# solar.net
KiCad netlist of a schematic drawn in EAGLE
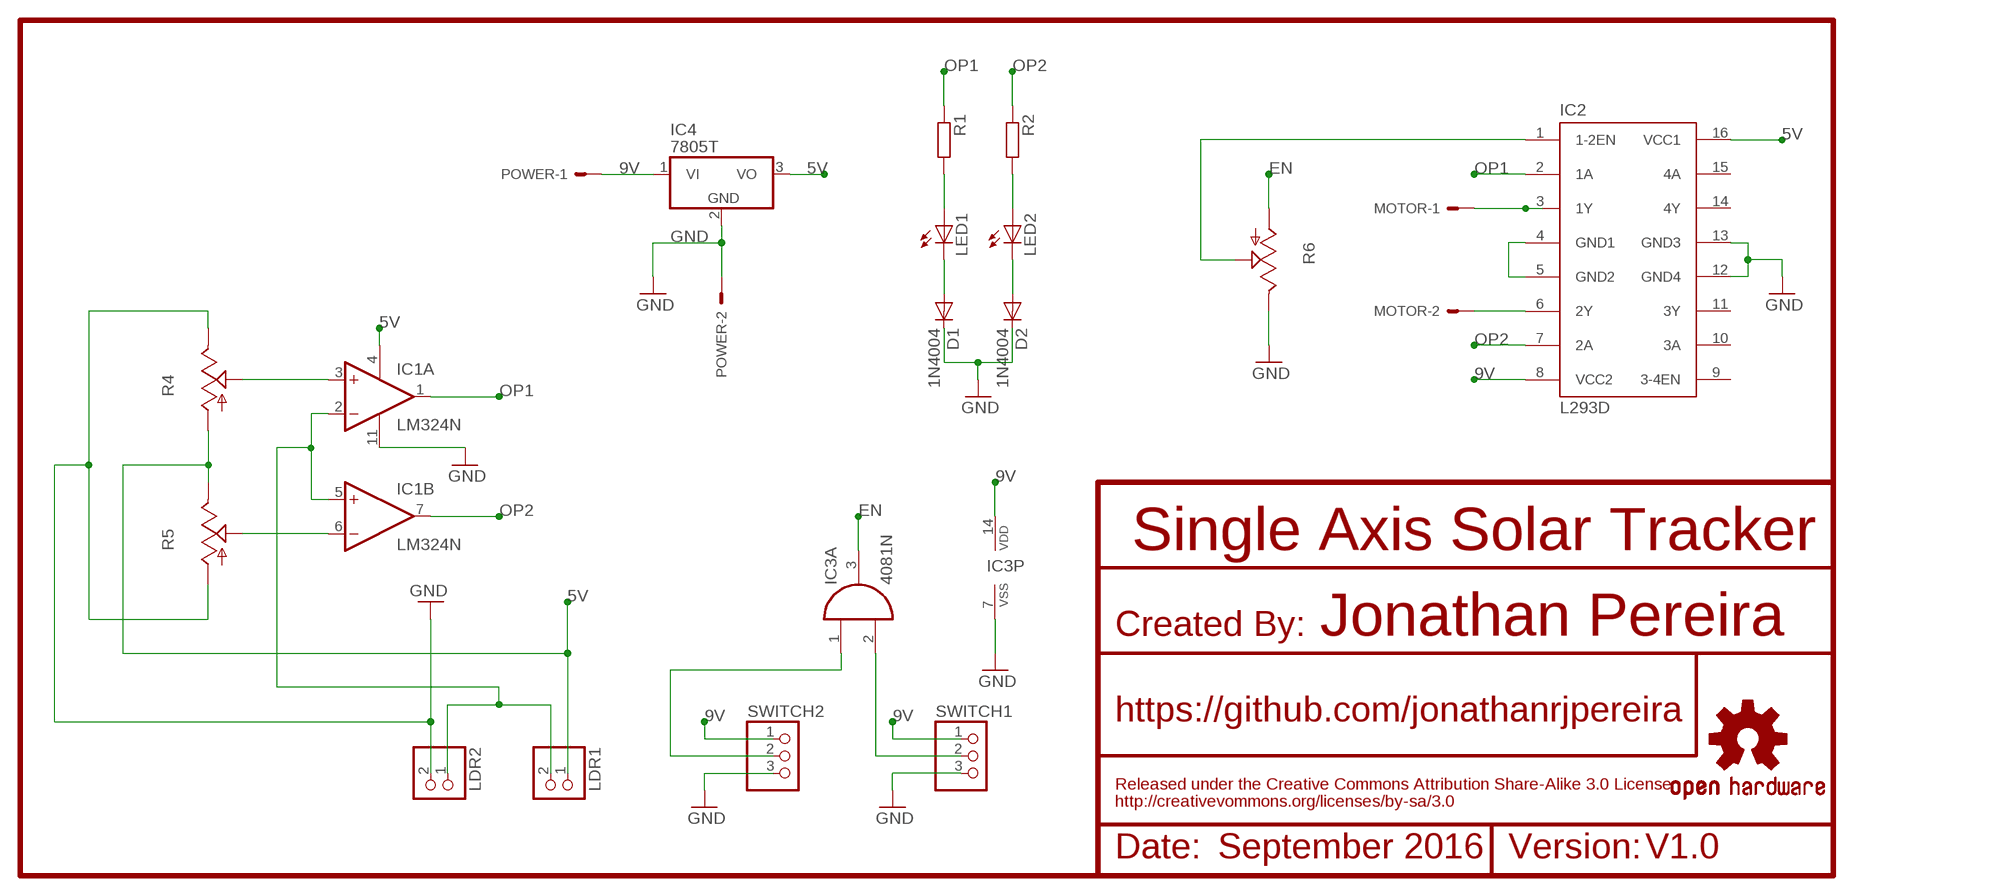
[diagram p0: schematic, sheet 1]

(export (version "E")
  (design (tool "Eeschema 10.0.6"))
  (components
    (comp (ref "D1")
      (value "1N4004")
      (footprint "eagle-import:DO41-10")
      (libsource (lib "eagle-import") (part "1N4004"))
    )
    (comp (ref "D2")
      (value "1N4004")
      (footprint "eagle-import:DO41-10")
      (libsource (lib "eagle-import") (part "1N4004"))
    )
    (comp (ref "IC1")
      (value "LM324N")
      (footprint "eagle-import:DIL14")
      (libsource (lib "eagle-import") (part "LM324N"))
    )
    (comp (ref "IC2")
      (value "L293D")
      (footprint "eagle-import:DIL16")
      (libsource (lib "eagle-import") (part "L293D"))
    )
    (comp (ref "IC3")
      (value "4081N")
      (footprint "eagle-import:DIL14")
      (libsource (lib "eagle-import") (part "4081N"))
    )
    (comp (ref "IC4")
      (value "7805T")
      (footprint "eagle-import:TO220H")
      (libsource (lib "eagle-import") (part "78T05"))
    )
    (comp (ref "LDR1")
      (value "PINHD-1X2")
      (footprint "eagle-import:1X02")
      (libsource (lib "eagle-import") (part "PINHD-1X2"))
    )
    (comp (ref "LDR2")
      (value "PINHD-1X2")
      (footprint "eagle-import:1X02")
      (libsource (lib "eagle-import") (part "PINHD-1X2"))
    )
    (comp (ref "LED1")
      (value "LED5MM")
      (footprint "eagle-import:LED5MM")
      (libsource (lib "eagle-import") (part "LED5MM"))
    )
    (comp (ref "LED2")
      (value "LED5MM")
      (footprint "eagle-import:LED5MM")
      (libsource (lib "eagle-import") (part "LED5MM"))
    )
    (comp (ref "LOGO1")
      (value "OSHW-LOGOL-COPPER")
      (footprint "eagle-import:OSHW-LOGO-L_COPPER")
      (libsource (lib "eagle-import") (part "OSHW-LOGOL-COPPER"))
    )
    (comp (ref "MOTOR")
      (value "KK-156-2")
      (footprint "eagle-import:KK-156-2")
      (libsource (lib "eagle-import") (part "KK-156-2"))
    )
    (comp (ref "POWER")
      (value "KK-156-2")
      (footprint "eagle-import:KK-156-2")
      (libsource (lib "eagle-import") (part "KK-156-2"))
    )
    (comp (ref "R1")
      (value "R-EU_0204/7")
      (footprint "eagle-import:0204_7")
      (libsource (lib "eagle-import") (part "R-EU_0204/7"))
    )
    (comp (ref "R2")
      (value "R-EU_0204/7")
      (footprint "eagle-import:0204_7")
      (libsource (lib "eagle-import") (part "R-EU_0204/7"))
    )
    (comp (ref "R4")
      (value "TRIM_US-CA6V")
      (footprint "eagle-import:CA6V")
      (libsource (lib "eagle-import") (part "TRIM_US-CA6V"))
    )
    (comp (ref "R5")
      (value "TRIM_US-CA6V")
      (footprint "eagle-import:CA6V")
      (libsource (lib "eagle-import") (part "TRIM_US-CA6V"))
    )
    (comp (ref "R6")
      (value "TRIM_US-CA6V")
      (footprint "eagle-import:CA6V")
      (libsource (lib "eagle-import") (part "TRIM_US-CA6V"))
    )
    (comp (ref "SWITCH1")
      (value "PINHD-1X3")
      (footprint "eagle-import:1X03")
      (libsource (lib "eagle-import") (part "PINHD-1X3"))
    )
    (comp (ref "SWITCH2")
      (value "PINHD-1X3")
      (footprint "eagle-import:1X03")
      (libsource (lib "eagle-import") (part "PINHD-1X3"))
    )
  )
  (nets
    (net (code "1") (name "/5V") (class "Default")
      (node (ref "IC1") (pin "4") (pinfunction "V+_4") (pintype "power_in"))
      (node (ref "IC2") (pin "16") (pinfunction "VCC1_16") (pintype "power_in"))
      (node (ref "IC4") (pin "3") (pinfunction "VO_3") (pintype "passive"))
      (node (ref "LDR1") (pin "1") (pinfunction "1_1") (pintype "passive"))
      (node (ref "R4") (pin "A") (pinfunction "A_A") (pintype "passive"))
      (node (ref "R5") (pin "E") (pinfunction "E_E") (pintype "passive"))
    )
    (net (code "2") (name "/9V") (class "Default")
      (node (ref "IC2") (pin "8") (pinfunction "VCC2_8") (pintype "power_in"))
      (node (ref "IC3") (pin "14") (pinfunction "VDD_14") (pintype "power_in"))
      (node (ref "IC4") (pin "1") (pinfunction "VI_1") (pintype "input"))
      (node (ref "POWER") (pin "1") (pinfunction "S_1") (pintype "passive"))
      (node (ref "SWITCH1") (pin "1") (pinfunction "1_1") (pintype "passive"))
      (node (ref "SWITCH2") (pin "1") (pinfunction "1_1") (pintype "passive"))
    )
    (net (code "3") (name "/EN") (class "Default")
      (node (ref "IC3") (pin "3") (pinfunction "O_3") (pintype "output"))
      (node (ref "R6") (pin "A") (pinfunction "A_A") (pintype "passive"))
    )
    (net (code "4") (name "/OP1") (class "Default")
      (node (ref "IC1") (pin "1") (pinfunction "OUT_1") (pintype "output"))
      (node (ref "IC2") (pin "2") (pinfunction "1A_2") (pintype "input"))
      (node (ref "R1") (pin "1") (pinfunction "1_1") (pintype "passive"))
    )
    (net (code "5") (name "/OP2") (class "Default")
      (node (ref "IC1") (pin "7") (pinfunction "OUT_7") (pintype "output"))
      (node (ref "IC2") (pin "7") (pinfunction "2A_7") (pintype "input"))
      (node (ref "R2") (pin "1") (pinfunction "1_1") (pintype "passive"))
    )
    (net (code "6") (name "GND") (class "Default")
      (node (ref "D1") (pin "C") (pinfunction "C_C") (pintype "passive"))
      (node (ref "D2") (pin "C") (pinfunction "C_C") (pintype "passive"))
      (node (ref "IC1") (pin "11") (pinfunction "V-_11") (pintype "power_in"))
      (node (ref "IC2") (pin "12") (pinfunction "GND4_12") (pintype "power_in"))
      (node (ref "IC2") (pin "13") (pinfunction "GND3_13") (pintype "power_in"))
      (node (ref "IC3") (pin "7") (pinfunction "VSS_7") (pintype "power_in"))
      (node (ref "IC4") (pin "2") (pinfunction "GND_2") (pintype "passive"))
      (node (ref "LDR2") (pin "2") (pinfunction "2_2") (pintype "passive"))
      (node (ref "POWER") (pin "2") (pinfunction "S_2") (pintype "passive"))
      (node (ref "R4") (pin "E") (pinfunction "E_E") (pintype "passive"))
      (node (ref "R5") (pin "A") (pinfunction "A_A") (pintype "passive"))
      (node (ref "R6") (pin "E") (pinfunction "E_E") (pintype "passive"))
      (node (ref "SWITCH1") (pin "3") (pinfunction "3_3") (pintype "passive"))
      (node (ref "SWITCH2") (pin "3") (pinfunction "3_3") (pintype "passive"))
    )
    (net (code "7") (name "Net-(IC1A-+IN)") (class "Default")
      (node (ref "IC1") (pin "3") (pinfunction "+IN_3") (pintype "input"))
      (node (ref "R4") (pin "S") (pinfunction "S_S") (pintype "passive"))
    )
    (net (code "8") (name "Net-(IC1A--IN)") (class "Default")
      (node (ref "IC1") (pin "2") (pinfunction "-IN_2") (pintype "input"))
      (node (ref "IC1") (pin "5") (pinfunction "+IN_5") (pintype "input"))
      (node (ref "LDR1") (pin "2") (pinfunction "2_2") (pintype "passive"))
      (node (ref "LDR2") (pin "1") (pinfunction "1_1") (pintype "passive"))
    )
    (net (code "9") (name "Net-(IC1B--IN)") (class "Default")
      (node (ref "IC1") (pin "6") (pinfunction "-IN_6") (pintype "input"))
      (node (ref "R5") (pin "S") (pinfunction "S_S") (pintype "passive"))
    )
    (net (code "10") (name "Net-(IC2-1-2EN)") (class "Default")
      (node (ref "IC2") (pin "1") (pinfunction "1-2EN_1") (pintype "input"))
      (node (ref "R6") (pin "S") (pinfunction "S_S") (pintype "passive"))
    )
    (net (code "11") (name "Net-(IC2-1Y)") (class "Default")
      (node (ref "IC2") (pin "3") (pinfunction "1Y_3") (pintype "output"))
      (node (ref "MOTOR") (pin "1") (pinfunction "S_1") (pintype "passive"))
    )
    (net (code "12") (name "Net-(IC2-2Y)") (class "Default")
      (node (ref "IC2") (pin "6") (pinfunction "2Y_6") (pintype "output"))
      (node (ref "MOTOR") (pin "2") (pinfunction "S_2") (pintype "passive"))
    )
    (net (code "13") (name "Net-(IC2-GND1)") (class "Default")
      (node (ref "IC2") (pin "4") (pinfunction "GND1_4") (pintype "power_in"))
      (node (ref "IC2") (pin "5") (pinfunction "GND2_5") (pintype "power_in"))
    )
    (net (code "14") (name "Net-(IC3A-I0)") (class "Default")
      (node (ref "IC3") (pin "1") (pinfunction "I0_1") (pintype "input"))
      (node (ref "SWITCH2") (pin "2") (pinfunction "2_2") (pintype "passive"))
    )
    (net (code "15") (name "Net-(IC3A-I1)") (class "Default")
      (node (ref "IC3") (pin "2") (pinfunction "I1_2") (pintype "input"))
      (node (ref "SWITCH1") (pin "2") (pinfunction "2_2") (pintype "passive"))
    )
    (net (code "16") (name "Net-(LED1-C)") (class "Default")
      (node (ref "D1") (pin "A") (pinfunction "A_A") (pintype "passive"))
      (node (ref "LED1") (pin "K") (pinfunction "C_K") (pintype "passive"))
    )
    (net (code "17") (name "Net-(LED1-PadA)") (class "Default")
      (node (ref "LED1") (pin "A") (pinfunction "A_A") (pintype "passive"))
      (node (ref "R1") (pin "2") (pinfunction "2_2") (pintype "passive"))
    )
    (net (code "18") (name "Net-(LED2-C)") (class "Default")
      (node (ref "D2") (pin "A") (pinfunction "A_A") (pintype "passive"))
      (node (ref "LED2") (pin "K") (pinfunction "C_K") (pintype "passive"))
    )
    (net (code "19") (name "Net-(LED2-PadA)") (class "Default")
      (node (ref "LED2") (pin "A") (pinfunction "A_A") (pintype "passive"))
      (node (ref "R2") (pin "2") (pinfunction "2_2") (pintype "passive"))
    )
    (net (code "20") (name "unconnected-(IC2-3-4EN-Pad9)") (class "Default")
      (node (ref "IC2") (pin "9") (pinfunction "3-4EN_9") (pintype "input"))
    )
    (net (code "21") (name "unconnected-(IC2-3A-Pad10)") (class "Default")
      (node (ref "IC2") (pin "10") (pinfunction "3A_10") (pintype "input"))
    )
    (net (code "22") (name "unconnected-(IC2-3Y-Pad11)") (class "Default")
      (node (ref "IC2") (pin "11") (pinfunction "3Y_11") (pintype "output"))
    )
    (net (code "23") (name "unconnected-(IC2-4A-Pad15)") (class "Default")
      (node (ref "IC2") (pin "15") (pinfunction "4A_15") (pintype "input"))
    )
    (net (code "24") (name "unconnected-(IC2-4Y-Pad14)") (class "Default")
      (node (ref "IC2") (pin "14") (pinfunction "4Y_14") (pintype "output"))
    )
  )
)
